# HeadBoard.net
KiCad netlist of a schematic drawn in EAGLE
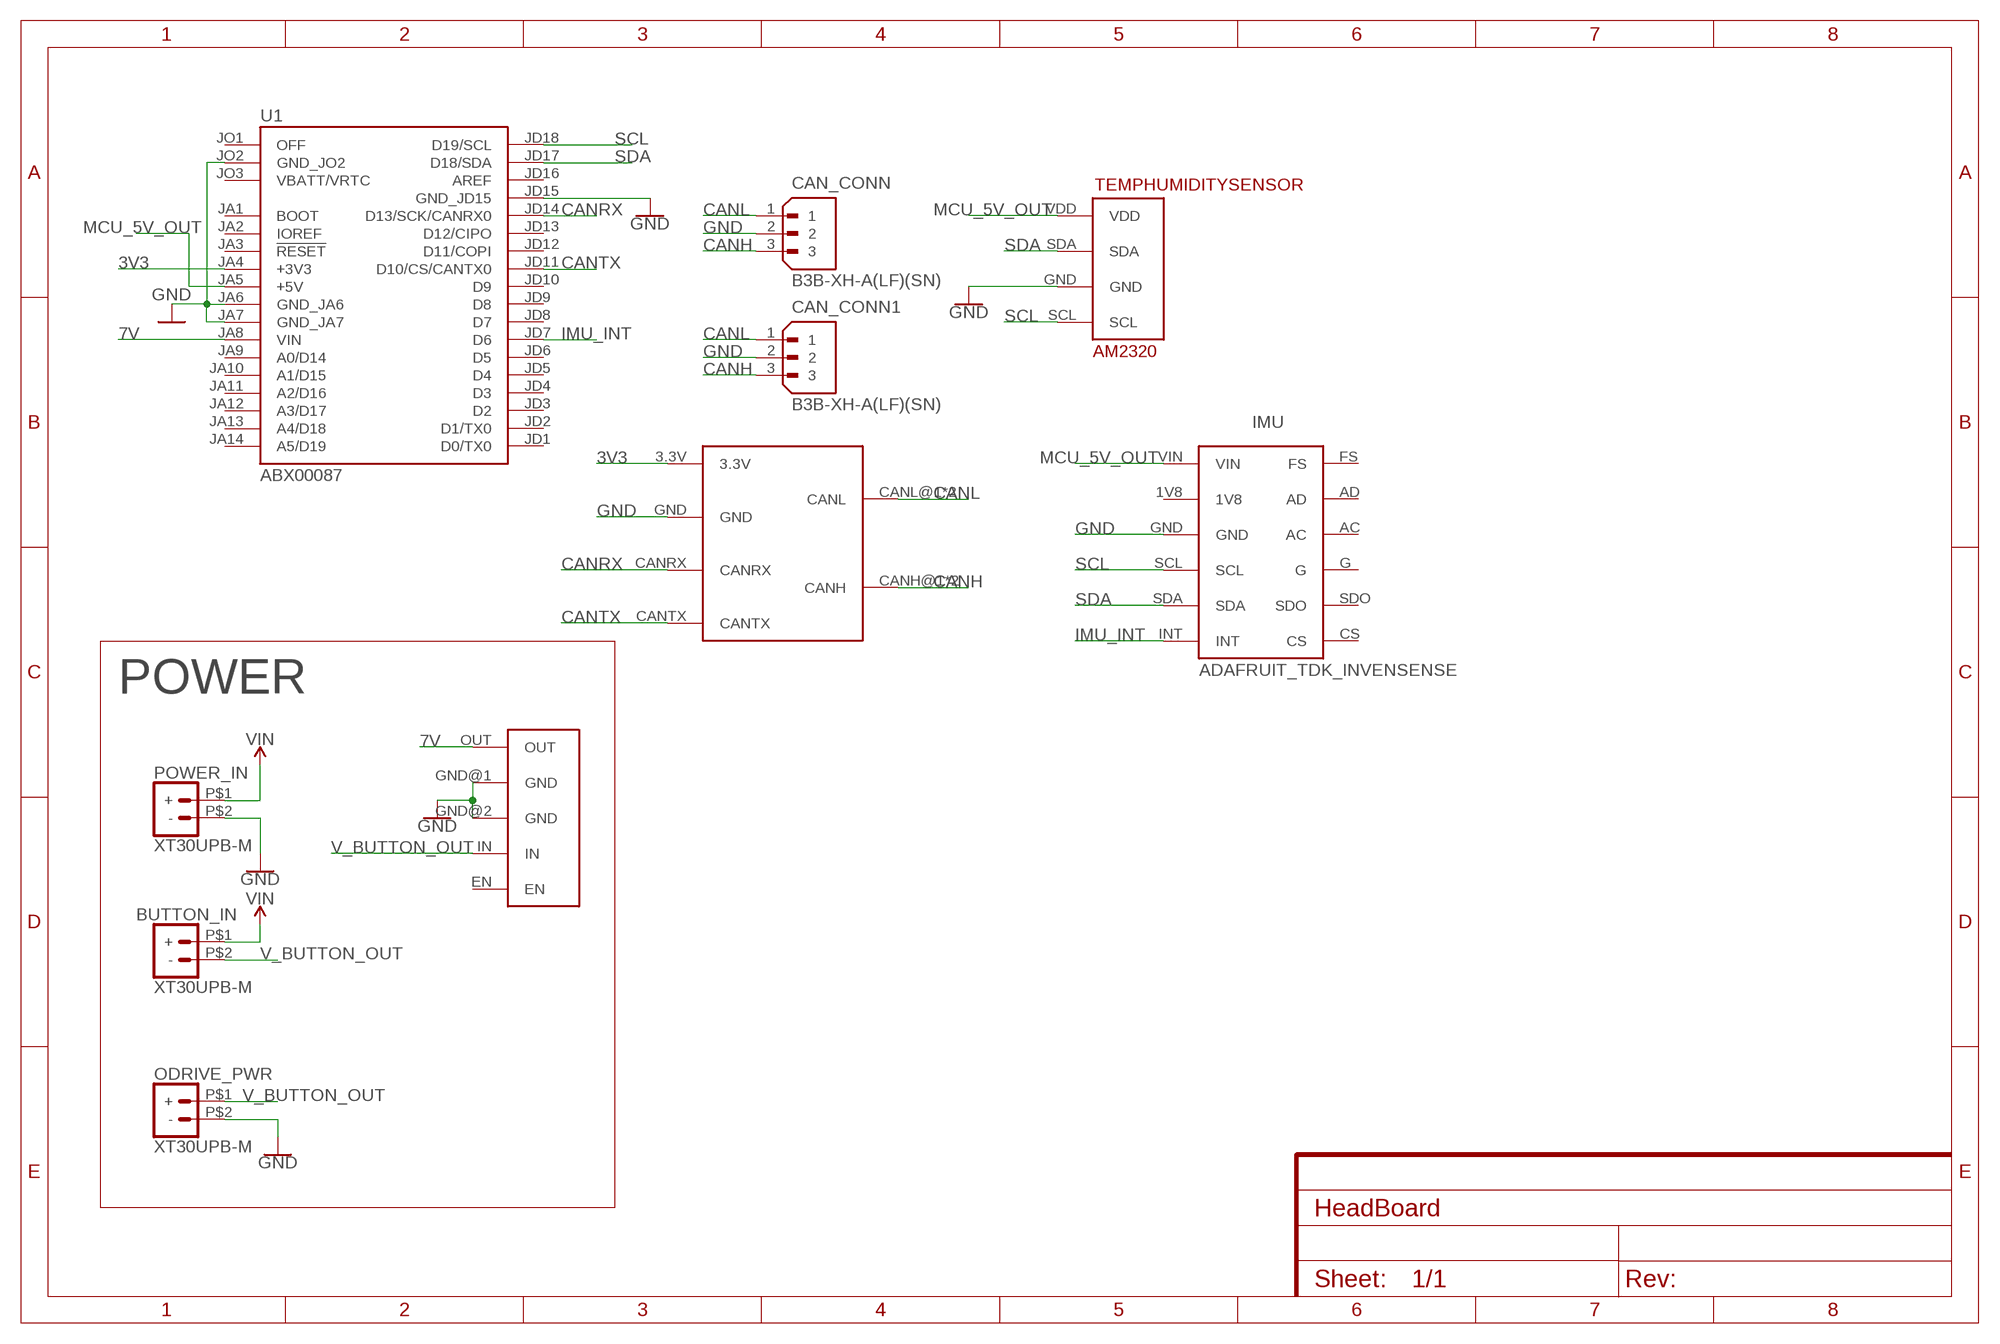
[diagram p0: schematic, sheet 1]

(export (version "E")
  (design (tool "Eeschema 10.0.6"))
  (components
    (comp (ref "BUTTON_IN")
      (value "XT30UPB-M")
      (footprint "eagle-import:XT30UPB-M")
      (fields (field (name "MF") "amass"))
      (libsource (lib "eagle-import") (part "XT30UPB-M"))
    )
    (comp (ref "CAN_CONN")
      (value "B3B-XH-A(LF)(SN)")
      (footprint "eagle-import:JST_B3B-XH-A(LF)(SN)")
      (fields (field (name "MF") "JST Sales"))
      (libsource (lib "eagle-import") (part "B3B-XH-A(LF)(SN)"))
    )
    (comp (ref "CAN_CONN1")
      (value "B3B-XH-A(LF)(SN)")
      (footprint "eagle-import:JST_B3B-XH-A(LF)(SN)")
      (fields (field (name "MF") "JST Sales"))
      (libsource (lib "eagle-import") (part "B3B-XH-A(LF)(SN)"))
    )
    (comp (ref "IMU")
      (value "ADAFRUIT_TDK_INVENSENSE")
      (footprint "eagle-import:ADAFRUIT_TDK_INVENSENSE")
      (libsource (lib "eagle-import") (part "ADAFRUIT_TDK_INVENSENSE"))
    )
    (comp (ref "ODRIVE_PWR")
      (value "XT30UPB-M")
      (footprint "eagle-import:XT30UPB-M")
      (fields (field (name "MF") "amass"))
      (libsource (lib "eagle-import") (part "XT30UPB-M"))
    )
    (comp (ref "POWER_IN")
      (value "XT30UPB-M")
      (footprint "eagle-import:XT30UPB-M")
      (fields (field (name "MF") "amass"))
      (libsource (lib "eagle-import") (part "XT30UPB-M"))
    )
    (comp (ref "TEMPHUMIDITYSENSOR")
      (value "AM2320")
      (footprint "eagle-import:AM2320")
      (libsource (lib "eagle-import") (part "AM2320"))
    )
    (comp (ref "U$1")
      (value "D36V28F7")
      (footprint "eagle-import:D36V28F5")
      (libsource (lib "eagle-import") (part "D36V28F7"))
    )
    (comp (ref "U$2")
      (value "WAVESHARE_SN65HVD230")
      (footprint "eagle-import:WAVESHARE_SN65HVD230")
      (libsource (lib "eagle-import") (part "WAVESHARE_SN65HVD230"))
    )
    (comp (ref "U1")
      (value "ABX00087")
      (footprint "eagle-import:MODULE_ABX00087")
      (fields (field (name "MANUFACTURER") "Arduino"))
      (libsource (lib "eagle-import") (part "ABX00087"))
    )
  )
  (nets
    (net (code "1") (name "/3V3") (class "Default")
      (node (ref "U$2") (pin "3.3V") (pinfunction "3.3V_3.3V") (pintype "bidirectional"))
      (node (ref "U1") (pin "JA4") (pinfunction "+3V3_JA4") (pintype "power_in"))
    )
    (net (code "2") (name "/7V") (class "Default")
      (node (ref "U$1") (pin "OUT") (pinfunction "OUT_OUT") (pintype "bidirectional"))
      (node (ref "U1") (pin "JA8") (pinfunction "VIN_JA8") (pintype "power_in"))
    )
    (net (code "3") (name "/CANH") (class "Default")
      (node (ref "CAN_CONN") (pin "3") (pinfunction "3_3") (pintype "passive"))
      (node (ref "CAN_CONN1") (pin "3") (pinfunction "3_3") (pintype "passive"))
      (node (ref "U$2") (pin "CANH@1") (pinfunction "CANH_CANH@1") (pintype "bidirectional"))
      (node (ref "U$2") (pin "CANH@2") (pinfunction "CANH_CANH@2") (pintype "bidirectional"))
    )
    (net (code "4") (name "/CANL") (class "Default")
      (node (ref "CAN_CONN") (pin "1") (pinfunction "1_1") (pintype "passive"))
      (node (ref "CAN_CONN1") (pin "1") (pinfunction "1_1") (pintype "passive"))
      (node (ref "U$2") (pin "CANL@1") (pinfunction "CANL_CANL@1") (pintype "bidirectional"))
      (node (ref "U$2") (pin "CANL@2") (pinfunction "CANL_CANL@2") (pintype "bidirectional"))
    )
    (net (code "5") (name "/CANRX") (class "Default")
      (node (ref "U$2") (pin "CANRX") (pinfunction "CANRX_CANRX") (pintype "bidirectional"))
      (node (ref "U1") (pin "JD14") (pinfunction "D13/SCK/CANRX0_JD14") (pintype "bidirectional"))
    )
    (net (code "6") (name "/CANTX") (class "Default")
      (node (ref "U$2") (pin "CANTX") (pinfunction "CANTX_CANTX") (pintype "bidirectional"))
      (node (ref "U1") (pin "JD11") (pinfunction "D10/CS/CANTX0_JD11") (pintype "bidirectional"))
    )
    (net (code "7") (name "/IMU_INT") (class "Default")
      (node (ref "IMU") (pin "INT") (pinfunction "INT_INT") (pintype "bidirectional"))
      (node (ref "U1") (pin "JD7") (pinfunction "D6_JD7") (pintype "bidirectional"))
    )
    (net (code "8") (name "/MCU_5V_OUT") (class "Default")
      (node (ref "IMU") (pin "VIN") (pinfunction "VIN_VIN") (pintype "bidirectional"))
      (node (ref "TEMPHUMIDITYSENSOR") (pin "VDD") (pinfunction "VDD_VDD") (pintype "bidirectional"))
      (node (ref "U1") (pin "JA5") (pinfunction "+5V_JA5") (pintype "power_in"))
    )
    (net (code "9") (name "/SCL") (class "Default")
      (node (ref "IMU") (pin "SCL") (pinfunction "SCL_SCL") (pintype "bidirectional"))
      (node (ref "TEMPHUMIDITYSENSOR") (pin "SCL") (pinfunction "SCL_SCL") (pintype "bidirectional"))
      (node (ref "U1") (pin "JD18") (pinfunction "D19/SCL_JD18") (pintype "bidirectional"))
    )
    (net (code "10") (name "/SDA") (class "Default")
      (node (ref "IMU") (pin "SDA") (pinfunction "SDA_SDA") (pintype "bidirectional"))
      (node (ref "TEMPHUMIDITYSENSOR") (pin "SDA") (pinfunction "SDA_SDA") (pintype "bidirectional"))
      (node (ref "U1") (pin "JD17") (pinfunction "D18/SDA_JD17") (pintype "bidirectional"))
    )
    (net (code "11") (name "/VBATT{slash}VRTC") (class "Default")
      (node (ref "U1") (pin "JO3") (pinfunction "VBATT/VRTC_JO3") (pintype "power_in"))
    )
    (net (code "12") (name "/V_BUTTON_OUT") (class "Default")
      (node (ref "BUTTON_IN") (pin "P$2") (pinfunction "-_P$2") (pintype "passive"))
      (node (ref "ODRIVE_PWR") (pin "P$1") (pinfunction "+_P$1") (pintype "passive"))
      (node (ref "U$1") (pin "IN") (pinfunction "IN_IN") (pintype "bidirectional"))
    )
    (net (code "13") (name "GND") (class "Default")
      (node (ref "CAN_CONN") (pin "2") (pinfunction "2_2") (pintype "passive"))
      (node (ref "CAN_CONN1") (pin "2") (pinfunction "2_2") (pintype "passive"))
      (node (ref "IMU") (pin "GND") (pinfunction "GND_GND") (pintype "bidirectional"))
      (node (ref "ODRIVE_PWR") (pin "P$2") (pinfunction "-_P$2") (pintype "passive"))
      (node (ref "POWER_IN") (pin "P$2") (pinfunction "-_P$2") (pintype "passive"))
      (node (ref "TEMPHUMIDITYSENSOR") (pin "GND") (pinfunction "GND_GND") (pintype "bidirectional"))
      (node (ref "U$1") (pin "GND@1") (pinfunction "GND_GND@1") (pintype "bidirectional"))
      (node (ref "U$1") (pin "GND@2") (pinfunction "GND_GND@2") (pintype "bidirectional"))
      (node (ref "U$2") (pin "GND") (pinfunction "GND_GND") (pintype "bidirectional"))
      (node (ref "U1") (pin "JA6") (pinfunction "GND_JA6_JA6") (pintype "power_in"))
      (node (ref "U1") (pin "JA7") (pinfunction "GND_JA7_JA7") (pintype "power_in"))
      (node (ref "U1") (pin "JD15") (pinfunction "GND_JD15_JD15") (pintype "power_in"))
      (node (ref "U1") (pin "JO2") (pinfunction "GND_JO2_JO2") (pintype "power_in"))
    )
    (net (code "14") (name "VIN") (class "Default")
      (node (ref "BUTTON_IN") (pin "P$1") (pinfunction "+_P$1") (pintype "passive"))
      (node (ref "POWER_IN") (pin "P$1") (pinfunction "+_P$1") (pintype "passive"))
    )
    (net (code "15") (name "unconnected-(IMU-Pad1V8)") (class "Default")
      (node (ref "IMU") (pin "1V8") (pinfunction "1V8_1V8") (pintype "bidirectional"))
    )
    (net (code "16") (name "unconnected-(IMU-PadAC)") (class "Default")
      (node (ref "IMU") (pin "AC") (pinfunction "AC_AC") (pintype "bidirectional"))
    )
    (net (code "17") (name "unconnected-(IMU-PadAD)") (class "Default")
      (node (ref "IMU") (pin "AD") (pinfunction "AD_AD") (pintype "bidirectional"))
    )
    (net (code "18") (name "unconnected-(IMU-PadCS)") (class "Default")
      (node (ref "IMU") (pin "CS") (pinfunction "CS_CS") (pintype "bidirectional"))
    )
    (net (code "19") (name "unconnected-(IMU-PadFS)") (class "Default")
      (node (ref "IMU") (pin "FS") (pinfunction "FS_FS") (pintype "bidirectional"))
    )
    (net (code "20") (name "unconnected-(IMU-PadG)") (class "Default")
      (node (ref "IMU") (pin "G") (pinfunction "G_G") (pintype "bidirectional"))
    )
    (net (code "21") (name "unconnected-(IMU-PadSDO)") (class "Default")
      (node (ref "IMU") (pin "SDO") (pinfunction "SDO_SDO") (pintype "bidirectional"))
    )
    (net (code "22") (name "unconnected-(U$1-PadEN)") (class "Default")
      (node (ref "U$1") (pin "EN") (pinfunction "EN_EN") (pintype "bidirectional"))
    )
    (net (code "23") (name "unconnected-(U1-A0{slash}D14-PadJA9)") (class "Default")
      (node (ref "U1") (pin "JA9") (pinfunction "A0/D14_JA9") (pintype "bidirectional"))
    )
    (net (code "24") (name "unconnected-(U1-A1{slash}D15-PadJA10)") (class "Default")
      (node (ref "U1") (pin "JA10") (pinfunction "A1/D15_JA10") (pintype "bidirectional"))
    )
    (net (code "25") (name "unconnected-(U1-A2{slash}D16-PadJA11)") (class "Default")
      (node (ref "U1") (pin "JA11") (pinfunction "A2/D16_JA11") (pintype "bidirectional"))
    )
    (net (code "26") (name "unconnected-(U1-A3{slash}D17-PadJA12)") (class "Default")
      (node (ref "U1") (pin "JA12") (pinfunction "A3/D17_JA12") (pintype "bidirectional"))
    )
    (net (code "27") (name "unconnected-(U1-A4{slash}D18-PadJA13)") (class "Default")
      (node (ref "U1") (pin "JA13") (pinfunction "A4/D18_JA13") (pintype "bidirectional"))
    )
    (net (code "28") (name "unconnected-(U1-A5{slash}D19-PadJA14)") (class "Default")
      (node (ref "U1") (pin "JA14") (pinfunction "A5/D19_JA14") (pintype "bidirectional"))
    )
    (net (code "29") (name "unconnected-(U1-AREF-PadJD16)") (class "Default")
      (node (ref "U1") (pin "JD16") (pinfunction "AREF_JD16") (pintype "input"))
    )
    (net (code "30") (name "unconnected-(U1-BOOT-PadJA1)") (class "Default")
      (node (ref "U1") (pin "JA1") (pinfunction "BOOT_JA1") (pintype "passive"))
    )
    (net (code "31") (name "unconnected-(U1-D0{slash}TX0-PadJD1)") (class "Default")
      (node (ref "U1") (pin "JD1") (pinfunction "D0/TX0_JD1") (pintype "bidirectional"))
    )
    (net (code "32") (name "unconnected-(U1-D1{slash}TX0-PadJD2)") (class "Default")
      (node (ref "U1") (pin "JD2") (pinfunction "D1/TX0_JD2") (pintype "bidirectional"))
    )
    (net (code "33") (name "unconnected-(U1-D2-PadJD3)") (class "Default")
      (node (ref "U1") (pin "JD3") (pinfunction "D2_JD3") (pintype "bidirectional"))
    )
    (net (code "34") (name "unconnected-(U1-D3-PadJD4)") (class "Default")
      (node (ref "U1") (pin "JD4") (pinfunction "D3_JD4") (pintype "bidirectional"))
    )
    (net (code "35") (name "unconnected-(U1-D4-PadJD5)") (class "Default")
      (node (ref "U1") (pin "JD5") (pinfunction "D4_JD5") (pintype "bidirectional"))
    )
    (net (code "36") (name "unconnected-(U1-D5-PadJD6)") (class "Default")
      (node (ref "U1") (pin "JD6") (pinfunction "D5_JD6") (pintype "bidirectional"))
    )
    (net (code "37") (name "unconnected-(U1-D7-PadJD8)") (class "Default")
      (node (ref "U1") (pin "JD8") (pinfunction "D7_JD8") (pintype "bidirectional"))
    )
    (net (code "38") (name "unconnected-(U1-D8-PadJD9)") (class "Default")
      (node (ref "U1") (pin "JD9") (pinfunction "D8_JD9") (pintype "bidirectional"))
    )
    (net (code "39") (name "unconnected-(U1-D9-PadJD10)") (class "Default")
      (node (ref "U1") (pin "JD10") (pinfunction "D9_JD10") (pintype "bidirectional"))
    )
    (net (code "40") (name "unconnected-(U1-D11{slash}COPI-PadJD12)") (class "Default")
      (node (ref "U1") (pin "JD12") (pinfunction "D11/COPI_JD12") (pintype "bidirectional"))
    )
    (net (code "41") (name "unconnected-(U1-D12{slash}CIPO-PadJD13)") (class "Default")
      (node (ref "U1") (pin "JD13") (pinfunction "D12/CIPO_JD13") (pintype "bidirectional"))
    )
    (net (code "42") (name "unconnected-(U1-IOREF-PadJA2)") (class "Default")
      (node (ref "U1") (pin "JA2") (pinfunction "IOREF_JA2") (pintype "input"))
    )
    (net (code "43") (name "unconnected-(U1-OFF-PadJO1)") (class "Default")
      (node (ref "U1") (pin "JO1") (pinfunction "OFF_JO1") (pintype "input"))
    )
    (net (code "44") (name "unconnected-(U1-~{RESET}-PadJA3)") (class "Default")
      (node (ref "U1") (pin "JA3") (pinfunction "~{RESET}_JA3") (pintype "input"))
    )
  )
)
